# attiny85_4Transistor.net
KiCad netlist of a schematic drawn in EAGLE
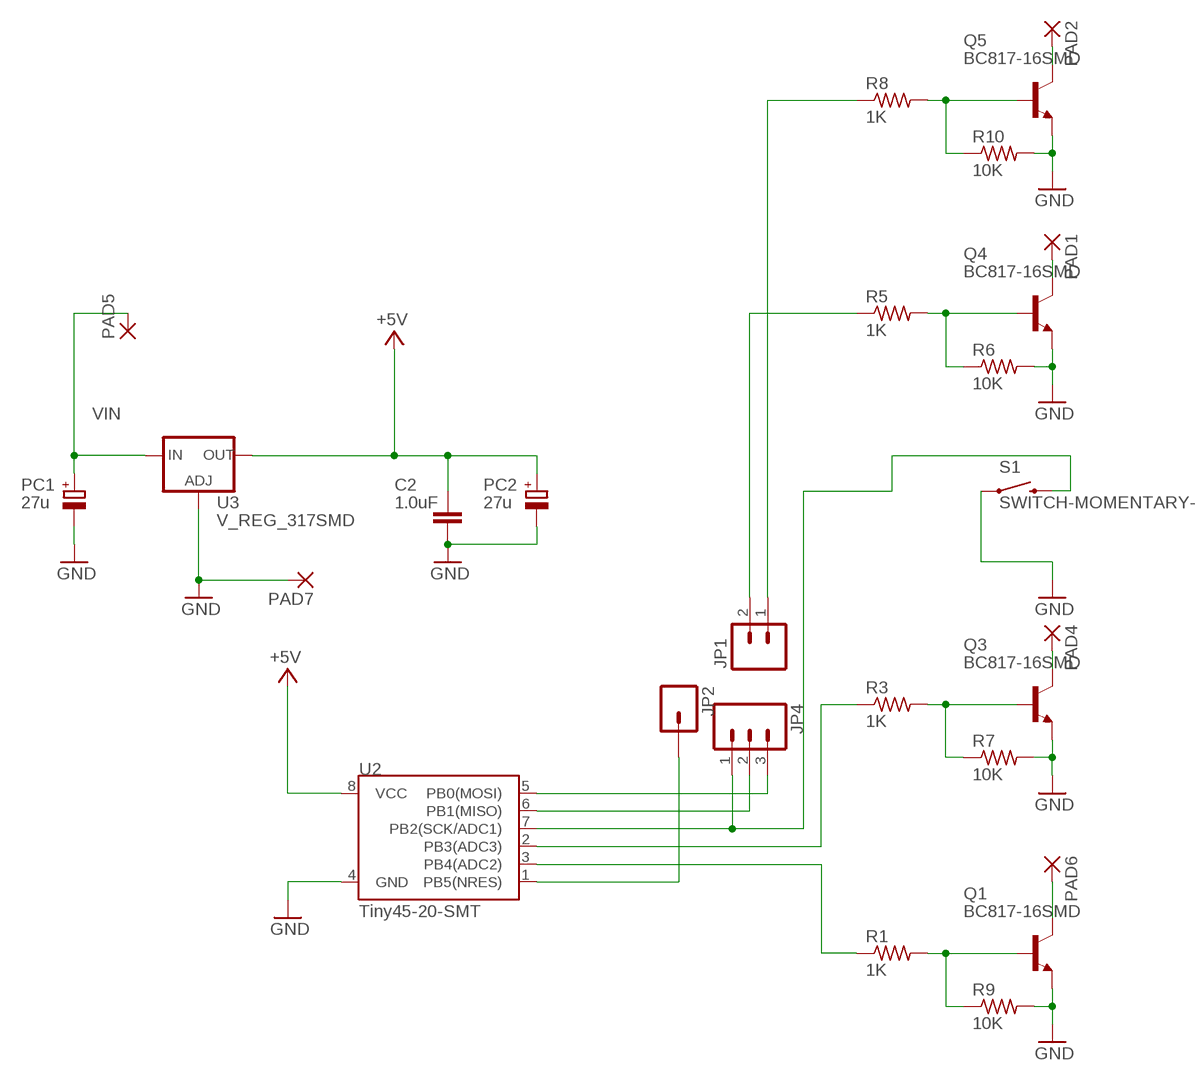
[diagram p0: schematic, sheet 1]

(export (version "E")
  (design (tool "Eeschema 10.0.6"))
  (components
    (comp (ref "C2")
      (value "1.0uF")
      (footprint "eagle-import:0805")
      (libsource (lib "eagle-import") (part "1.0UF-25V-+80/-20(0805)"))
    )
    (comp (ref "JP1")
      (value "M021X02_NO_SILK")
      (footprint "eagle-import:1X02_NO_SILK")
      (libsource (lib "eagle-import") (part "M021X02_NO_SILK"))
    )
    (comp (ref "JP2")
      (value "M01PTH")
      (footprint "eagle-import:1X01")
      (libsource (lib "eagle-import") (part "M01PTH"))
    )
    (comp (ref "JP4")
      (value "M031X03_NO_SILK")
      (footprint "eagle-import:1X03_NO_SILK")
      (libsource (lib "eagle-import") (part "M031X03_NO_SILK"))
    )
    (comp (ref "PAD1")
      (value "2,15/1,0")
      (footprint "eagle-import:2,15_1,0")
      (libsource (lib "eagle-import") (part "2,15/1,0"))
    )
    (comp (ref "PAD2")
      (value "2,15/1,0")
      (footprint "eagle-import:2,15_1,0")
      (libsource (lib "eagle-import") (part "2,15/1,0"))
    )
    (comp (ref "PAD4")
      (value "2,15/1,0")
      (footprint "eagle-import:2,15_1,0")
      (libsource (lib "eagle-import") (part "2,15/1,0"))
    )
    (comp (ref "PAD5")
      (value "2,15/1,0")
      (footprint "eagle-import:2,15_1,0")
      (libsource (lib "eagle-import") (part "2,15/1,0"))
    )
    (comp (ref "PAD6")
      (value "2,15/1,0")
      (footprint "eagle-import:2,15_1,0")
      (libsource (lib "eagle-import") (part "2,15/1,0"))
    )
    (comp (ref "PAD7")
      (value "2,15/1,0")
      (footprint "eagle-import:2,15_1,0")
      (libsource (lib "eagle-import") (part "2,15/1,0"))
    )
    (comp (ref "PC1")
      (value "27u")
      (footprint "eagle-import:E2,5-4R")
      (libsource (lib "eagle-import") (part "CPOL-EUE2.5-5V"))
    )
    (comp (ref "PC2")
      (value "27u")
      (footprint "eagle-import:E2,5-4R")
      (libsource (lib "eagle-import") (part "CPOL-EUE2.5-5V"))
    )
    (comp (ref "Q1")
      (value "BC817-16SMD")
      (footprint "eagle-import:SOT23-BEC")
      (libsource (lib "eagle-import") (part "BC817SMD-16"))
    )
    (comp (ref "Q3")
      (value "BC817-16SMD")
      (footprint "eagle-import:SOT23-BEC")
      (libsource (lib "eagle-import") (part "BC817SMD-16"))
    )
    (comp (ref "Q4")
      (value "BC817-16SMD")
      (footprint "eagle-import:SOT23-BEC")
      (libsource (lib "eagle-import") (part "BC817SMD-16"))
    )
    (comp (ref "Q5")
      (value "BC817-16SMD")
      (footprint "eagle-import:SOT23-BEC")
      (libsource (lib "eagle-import") (part "BC817SMD-16"))
    )
    (comp (ref "R1")
      (value "1K")
      (footprint "eagle-import:R0805")
      (libsource (lib "eagle-import") (part "rcl_R-US_R0805"))
    )
    (comp (ref "R3")
      (value "1K")
      (footprint "eagle-import:R0805")
      (libsource (lib "eagle-import") (part "rcl_R-US_R0805"))
    )
    (comp (ref "R5")
      (value "1K")
      (footprint "eagle-import:R0805")
      (libsource (lib "eagle-import") (part "rcl_R-US_R0805"))
    )
    (comp (ref "R6")
      (value "10K")
      (footprint "eagle-import:M0805")
      (libsource (lib "eagle-import") (part "R-US_M0805"))
    )
    (comp (ref "R7")
      (value "10K")
      (footprint "eagle-import:M0805")
      (libsource (lib "eagle-import") (part "R-US_M0805"))
    )
    (comp (ref "R8")
      (value "1K")
      (footprint "eagle-import:R0805")
      (libsource (lib "eagle-import") (part "rcl_R-US_R0805"))
    )
    (comp (ref "R9")
      (value "10K")
      (footprint "eagle-import:M0805")
      (libsource (lib "eagle-import") (part "R-US_M0805"))
    )
    (comp (ref "R10")
      (value "10K")
      (footprint "eagle-import:M0805")
      (libsource (lib "eagle-import") (part "R-US_M0805"))
    )
    (comp (ref "S1")
      (value "SWITCH-MOMENTARY-2")
      (footprint "eagle-import:TACTILE_FSM4JSMATR")
      (libsource (lib "eagle-import") (part "SWITCH-MOMENTARY-2"))
    )
    (comp (ref "U2")
      (value "Tiny45-20-SMT")
      (footprint "eagle-import:SO08-EIAJ")
      (libsource (lib "eagle-import") (part "ATTINY45TINY45-20-SMT"))
    )
    (comp (ref "U3")
      (value "V_REG_317SMD")
      (footprint "eagle-import:SOT223")
      (libsource (lib "eagle-import") (part "V_REG_317SMD"))
    )
  )
  (nets
    (net (code "1") (name "+5V") (class "Default")
      (node (ref "C2") (pin "2") (pinfunction "2_2") (pintype "passive"))
      (node (ref "PC2") (pin "+") (pinfunction "+_+") (pintype "passive"))
      (node (ref "U2") (pin "8") (pinfunction "VCC_8") (pintype "bidirectional"))
      (node (ref "U3") (pin "2") (pinfunction "OUT_2") (pintype "output"))
    )
    (net (code "2") (name "/VIN") (class "Default")
      (node (ref "PAD5") (pin "1") (pinfunction "P_1") (pintype "passive"))
      (node (ref "PC1") (pin "+") (pinfunction "+_+") (pintype "passive"))
      (node (ref "U3") (pin "3") (pinfunction "IN_3") (pintype "input"))
    )
    (net (code "3") (name "GND") (class "Default")
      (node (ref "C2") (pin "1") (pinfunction "1_1") (pintype "passive"))
      (node (ref "PAD7") (pin "1") (pinfunction "P_1") (pintype "passive"))
      (node (ref "PC1") (pin "-") (pinfunction "-_-") (pintype "passive"))
      (node (ref "PC2") (pin "-") (pinfunction "-_-") (pintype "passive"))
      (node (ref "Q1") (pin "E") (pinfunction "E_E") (pintype "passive"))
      (node (ref "Q3") (pin "E") (pinfunction "E_E") (pintype "passive"))
      (node (ref "Q4") (pin "E") (pinfunction "E_E") (pintype "passive"))
      (node (ref "Q5") (pin "E") (pinfunction "E_E") (pintype "passive"))
      (node (ref "R10") (pin "2") (pinfunction "2_2") (pintype "passive"))
      (node (ref "R6") (pin "2") (pinfunction "2_2") (pintype "passive"))
      (node (ref "R7") (pin "2") (pinfunction "2_2") (pintype "passive"))
      (node (ref "R9") (pin "2") (pinfunction "2_2") (pintype "passive"))
      (node (ref "S1") (pin "P$1") (pinfunction "1_P$1") (pintype "passive"))
      (node (ref "S1") (pin "P$2") (pinfunction "1_P$2") (pintype "passive"))
      (node (ref "U2") (pin "4") (pinfunction "GND_4") (pintype "bidirectional"))
      (node (ref "U3") (pin "1") (pinfunction "ADJ_1") (pintype "input"))
    )
    (net (code "4") (name "Net-(JP1-Pad1)") (class "Default")
      (node (ref "JP1") (pin "1") (pinfunction "1_1") (pintype "passive"))
      (node (ref "R8") (pin "1") (pinfunction "1_1") (pintype "passive"))
    )
    (net (code "5") (name "Net-(JP1-Pad2)") (class "Default")
      (node (ref "JP1") (pin "2") (pinfunction "2_2") (pintype "passive"))
      (node (ref "R5") (pin "1") (pinfunction "1_1") (pintype "passive"))
    )
    (net (code "6") (name "Net-(PAD1-P)") (class "Default")
      (node (ref "PAD1") (pin "1") (pinfunction "P_1") (pintype "passive"))
      (node (ref "Q4") (pin "C") (pinfunction "C_C") (pintype "passive"))
    )
    (net (code "7") (name "Net-(PAD2-P)") (class "Default")
      (node (ref "PAD2") (pin "1") (pinfunction "P_1") (pintype "passive"))
      (node (ref "Q5") (pin "C") (pinfunction "C_C") (pintype "passive"))
    )
    (net (code "8") (name "Net-(PAD4-P)") (class "Default")
      (node (ref "PAD4") (pin "1") (pinfunction "P_1") (pintype "passive"))
      (node (ref "Q3") (pin "C") (pinfunction "C_C") (pintype "passive"))
    )
    (net (code "9") (name "Net-(PAD6-P)") (class "Default")
      (node (ref "PAD6") (pin "1") (pinfunction "P_1") (pintype "passive"))
      (node (ref "Q1") (pin "C") (pinfunction "C_C") (pintype "passive"))
    )
    (net (code "10") (name "Net-(Q1-PadB)") (class "Default")
      (node (ref "Q1") (pin "B") (pinfunction "B_B") (pintype "passive"))
      (node (ref "R1") (pin "2") (pinfunction "2_2") (pintype "passive"))
      (node (ref "R9") (pin "1") (pinfunction "1_1") (pintype "passive"))
    )
    (net (code "11") (name "Net-(Q3-PadB)") (class "Default")
      (node (ref "Q3") (pin "B") (pinfunction "B_B") (pintype "passive"))
      (node (ref "R3") (pin "2") (pinfunction "2_2") (pintype "passive"))
      (node (ref "R7") (pin "1") (pinfunction "1_1") (pintype "passive"))
    )
    (net (code "12") (name "Net-(Q4-PadB)") (class "Default")
      (node (ref "Q4") (pin "B") (pinfunction "B_B") (pintype "passive"))
      (node (ref "R5") (pin "2") (pinfunction "2_2") (pintype "passive"))
      (node (ref "R6") (pin "1") (pinfunction "1_1") (pintype "passive"))
    )
    (net (code "13") (name "Net-(Q5-PadB)") (class "Default")
      (node (ref "Q5") (pin "B") (pinfunction "B_B") (pintype "passive"))
      (node (ref "R10") (pin "1") (pinfunction "1_1") (pintype "passive"))
      (node (ref "R8") (pin "2") (pinfunction "2_2") (pintype "passive"))
    )
    (net (code "14") (name "Net-(U2-PB0(MOSI))") (class "Default")
      (node (ref "JP4") (pin "3") (pinfunction "3_3") (pintype "passive"))
      (node (ref "U2") (pin "5") (pinfunction "PB0(MOSI)_5") (pintype "bidirectional"))
    )
    (net (code "15") (name "Net-(U2-PB1(MISO))") (class "Default")
      (node (ref "JP4") (pin "2") (pinfunction "2_2") (pintype "passive"))
      (node (ref "U2") (pin "6") (pinfunction "PB1(MISO)_6") (pintype "bidirectional"))
    )
    (net (code "16") (name "Net-(U2-PB2(SCK{slash}ADC1))") (class "Default")
      (node (ref "JP4") (pin "1") (pinfunction "1_1") (pintype "passive"))
      (node (ref "S1") (pin "P$3") (pinfunction "2_P$3") (pintype "passive"))
      (node (ref "S1") (pin "P$4") (pinfunction "2_P$4") (pintype "passive"))
      (node (ref "U2") (pin "7") (pinfunction "PB2(SCK/ADC1)_7") (pintype "bidirectional"))
    )
    (net (code "17") (name "Net-(U2-PB3(ADC3))") (class "Default")
      (node (ref "R3") (pin "1") (pinfunction "1_1") (pintype "passive"))
      (node (ref "U2") (pin "2") (pinfunction "PB3(ADC3)_2") (pintype "bidirectional"))
    )
    (net (code "18") (name "Net-(U2-PB4(ADC2))") (class "Default")
      (node (ref "R1") (pin "1") (pinfunction "1_1") (pintype "passive"))
      (node (ref "U2") (pin "3") (pinfunction "PB4(ADC2)_3") (pintype "bidirectional"))
    )
    (net (code "19") (name "Net-(U2-PB5(NRES))") (class "Default")
      (node (ref "JP2") (pin "1") (pinfunction "1_1") (pintype "passive"))
      (node (ref "U2") (pin "1") (pinfunction "PB5(NRES)_1") (pintype "bidirectional"))
    )
  )
)
